# VSENSE_EQ.net
KiCad netlist of a schematic drawn in Altium Designer
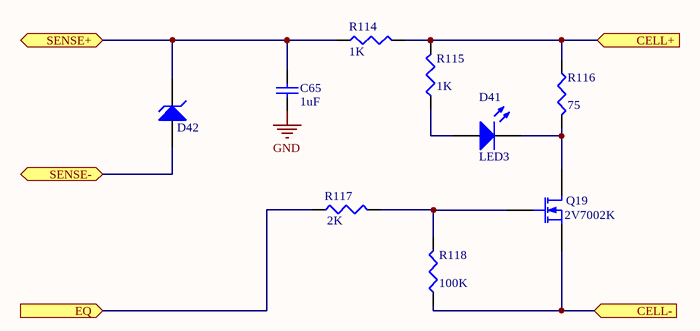
[diagram p0: VSENSE_EQ.SchDoc]

(export (version "E")
  (design (tool "Eeschema 10.0.6"))
  (components
    (comp (ref "C65")
      (value "1uF")
      (footprint "C1206")
      (description "Capacitor (Semiconductor SIM Model)")
      (fields (field (name "Comment") "Cap Semi") (field (name "PUBLISHER") "Altium Limited"))
      (libsource (lib "Miscellaneous Devices") (part "Cap Semi"))
    )
    (comp (ref "D41")
      (value "LED3")
      (footprint "516-1443-1-ND")
      (description "Typical BLUE SiC LED")
      (fields
        (field (name "MANUFACTURER") "Broadcom Avago")
        (field (name "MANUFACTURER PART NUMBER") "HSMG-C150")
        (field (name "PUBLISHER") "Altium Limited")
      )
      (libsource (lib "Miscellaneous Devices") (part "LED3"))
    )
    (comp (ref "D42")
      (value "D Zener")
      (footprint "ZENER DIODE")
      (description "Zener Diode")
      (fields
        (field (name "MANUFACTURER") "Diodes")
        (field (name "MANUFACTURER PART NUMBER") "DDZ6V2B-7")
        (field (name "PUBLISHER") "Altium Limited")
      )
      (libsource (lib "Miscellaneous Devices") (part "D Zener"))
    )
    (comp (ref "Q19")
      (value "2V7002K")
      (footprint "N-MOSFET")
      (description "N-Channel MOSFET")
      (fields
        (field (name "MANUFACTURER") "ON Semiconductor")
        (field (name "MANUFACTURER PART NUMBER") "2V7002KT1G")
        (field (name "PUBLISHER") "Altium Limited")
      )
      (libsource (lib "Miscellaneous Devices") (part "MOSFET-N"))
    )
    (comp (ref "R114")
      (value "1K")
      (footprint "0603 RES")
      (description "Resistor")
      (fields (field (name "Comment") "Res3") (field (name "PUBLISHER") "Altium Limited"))
      (libsource (lib "Miscellaneous Devices") (part "Res3"))
    )
    (comp (ref "R115")
      (value "1K")
      (footprint "0603 RES")
      (description "Resistor")
      (fields (field (name "Comment") "Res3") (field (name "PUBLISHER") "Altium Limited"))
      (libsource (lib "Miscellaneous Devices") (part "Res3"))
    )
    (comp (ref "R116")
      (value "75")
      (footprint "2512 RES")
      (description "Resistor")
      (fields
        (field (name "MANUFACTURER") "Vishay Dale")
        (field (name "MANUFACTURER PART NUMBER") "CRCW251275R0FKEG")
        (field (name "PUBLISHER") "Altium Limited")
      )
      (libsource (lib "Miscellaneous Devices") (part "Res3"))
    )
    (comp (ref "R117")
      (value "2K")
      (footprint "0603 RES")
      (description "Resistor")
      (fields (field (name "Comment") "Res3") (field (name "PUBLISHER") "Altium Limited"))
      (libsource (lib "Miscellaneous Devices") (part "Res3"))
    )
    (comp (ref "R118")
      (value "100K")
      (footprint "0603 RES")
      (description "Resistor")
      (fields (field (name "Comment") "Res3") (field (name "PUBLISHER") "Altium Limited"))
      (libsource (lib "Miscellaneous Devices") (part "Res3"))
    )
  )
  (nets
    (net (code "1") (name "/CELL+") (class "Default")
      (node (ref "R114") (pin "2") (pinfunction "2_2") (pintype "passive"))
      (node (ref "R115") (pin "2") (pinfunction "2_2") (pintype "passive"))
      (node (ref "R116") (pin "1") (pinfunction "1_1") (pintype "passive"))
    )
    (net (code "2") (name "/CELL-") (class "Default")
      (node (ref "Q19") (pin "3") (pinfunction "S_3") (pintype "passive"))
      (node (ref "R118") (pin "1") (pinfunction "1_1") (pintype "passive"))
    )
    (net (code "3") (name "/EQ") (class "Default")
      (node (ref "R117") (pin "1") (pinfunction "1_1") (pintype "passive"))
    )
    (net (code "4") (name "/SENSE+") (class "Default")
      (node (ref "C65") (pin "2") (pinfunction "2_2") (pintype "passive"))
      (node (ref "D42") (pin "2") (pinfunction "K_2") (pintype "passive"))
      (node (ref "R114") (pin "1") (pinfunction "1_1") (pintype "passive"))
    )
    (net (code "5") (name "/SENSE-") (class "Default")
      (node (ref "D42") (pin "1") (pinfunction "A_1") (pintype "passive"))
    )
    (net (code "6") (name "GND") (class "Default")
      (node (ref "C65") (pin "1") (pinfunction "1_1") (pintype "passive"))
    )
    (net (code "7") (name "Net-(D41-A)") (class "Default")
      (node (ref "D41") (pin "1") (pinfunction "A_1") (pintype "passive"))
      (node (ref "R115") (pin "1") (pinfunction "1_1") (pintype "passive"))
    )
    (net (code "8") (name "Net-(D41-K)") (class "Default")
      (node (ref "D41") (pin "2") (pinfunction "K_2") (pintype "passive"))
      (node (ref "Q19") (pin "1") (pinfunction "D_1") (pintype "passive"))
      (node (ref "R116") (pin "2") (pinfunction "2_2") (pintype "passive"))
    )
    (net (code "9") (name "Net-(Q19-G)") (class "Default")
      (node (ref "Q19") (pin "2") (pinfunction "G_2") (pintype "passive"))
      (node (ref "R117") (pin "2") (pinfunction "2_2") (pintype "passive"))
      (node (ref "R118") (pin "2") (pinfunction "2_2") (pintype "passive"))
    )
  )
)
